# 555_parpadeo.net
KiCad netlist of a schematic drawn in EAGLE
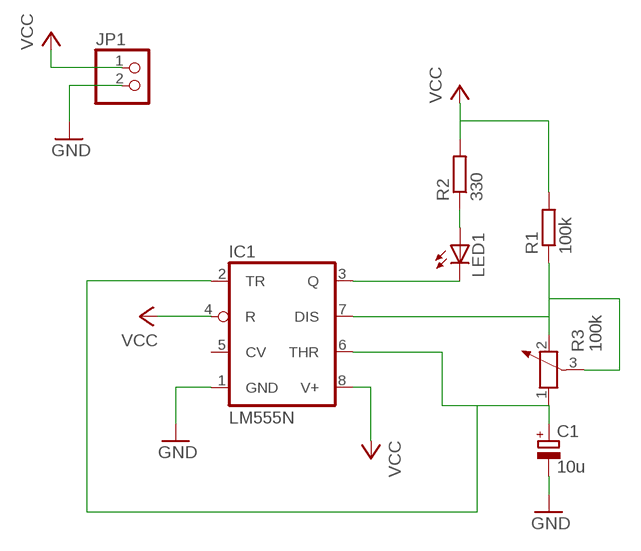
[diagram p0: schematic, sheet 1]

(export (version "E")
  (design (tool "Eeschema 10.0.6"))
  (components
    (comp (ref "C1")
      (value "10u")
      (footprint "eagle-import:E2,5-6")
      (libsource (lib "eagle-import") (part "CPOL-EUE2.5-6"))
    )
    (comp (ref "IC1")
      (value "LM555N")
      (footprint "eagle-import:DIL08")
      (libsource (lib "eagle-import") (part "555NLM"))
    )
    (comp (ref "JP1")
      (value "PINHD-1X2")
      (footprint "eagle-import:1X02")
      (libsource (lib "eagle-import") (part "PINHD-1X2"))
    )
    (comp (ref "LED1")
      (value "LED5MM")
      (footprint "eagle-import:LED5MM")
      (libsource (lib "eagle-import") (part "LED5MM"))
    )
    (comp (ref "R1")
      (value "100k")
      (footprint "eagle-import:0204_7")
      (libsource (lib "eagle-import") (part "R-EU_0204/7"))
    )
    (comp (ref "R2")
      (value "330")
      (footprint "eagle-import:0204_7")
      (libsource (lib "eagle-import") (part "R-EU_0204/7"))
    )
    (comp (ref "R3")
      (value "100k")
      (footprint "eagle-import:PT-10")
      (libsource (lib "eagle-import") (part "POTENTIOMETER_PT-10"))
    )
  )
  (nets
    (net (code "1") (name "GND") (class "Default")
      (node (ref "C1") (pin "-") (pinfunction "-_-") (pintype "passive"))
      (node (ref "IC1") (pin "1") (pinfunction "GND_1") (pintype "power_in"))
      (node (ref "JP1") (pin "2") (pinfunction "2_2") (pintype "passive"))
    )
    (net (code "2") (name "Net-(IC1-DIS)") (class "Default")
      (node (ref "IC1") (pin "7") (pinfunction "DIS_7") (pintype "input"))
      (node (ref "R1") (pin "1") (pinfunction "1_1") (pintype "passive"))
      (node (ref "R3") (pin "2") (pinfunction "2_2") (pintype "passive"))
      (node (ref "R3") (pin "3") (pinfunction "3_3") (pintype "passive"))
    )
    (net (code "3") (name "Net-(IC1-Q)") (class "Default")
      (node (ref "IC1") (pin "3") (pinfunction "Q_3") (pintype "output"))
      (node (ref "LED1") (pin "K") (pinfunction "C_K") (pintype "passive"))
    )
    (net (code "4") (name "Net-(IC1-THR)") (class "Default")
      (node (ref "C1") (pin "+") (pinfunction "+_+") (pintype "passive"))
      (node (ref "IC1") (pin "2") (pinfunction "TR_2") (pintype "input"))
      (node (ref "IC1") (pin "6") (pinfunction "THR_6") (pintype "input"))
      (node (ref "R3") (pin "1") (pinfunction "1_1") (pintype "passive"))
    )
    (net (code "5") (name "Net-(LED1-PadA)") (class "Default")
      (node (ref "LED1") (pin "A") (pinfunction "A_A") (pintype "passive"))
      (node (ref "R2") (pin "1") (pinfunction "1_1") (pintype "passive"))
    )
    (net (code "6") (name "VCC") (class "Default")
      (node (ref "IC1") (pin "4") (pinfunction "R_4") (pintype "input"))
      (node (ref "IC1") (pin "8") (pinfunction "V+_8") (pintype "power_in"))
      (node (ref "JP1") (pin "1") (pinfunction "1_1") (pintype "passive"))
      (node (ref "R1") (pin "2") (pinfunction "2_2") (pintype "passive"))
      (node (ref "R2") (pin "2") (pinfunction "2_2") (pintype "passive"))
    )
    (net (code "7") (name "unconnected-(IC1-CV-Pad5)") (class "Default")
      (node (ref "IC1") (pin "5") (pinfunction "CV_5") (pintype "input"))
    )
  )
)
